# FrontPanel.net
KiCad netlist of a schematic drawn in Altium Designer
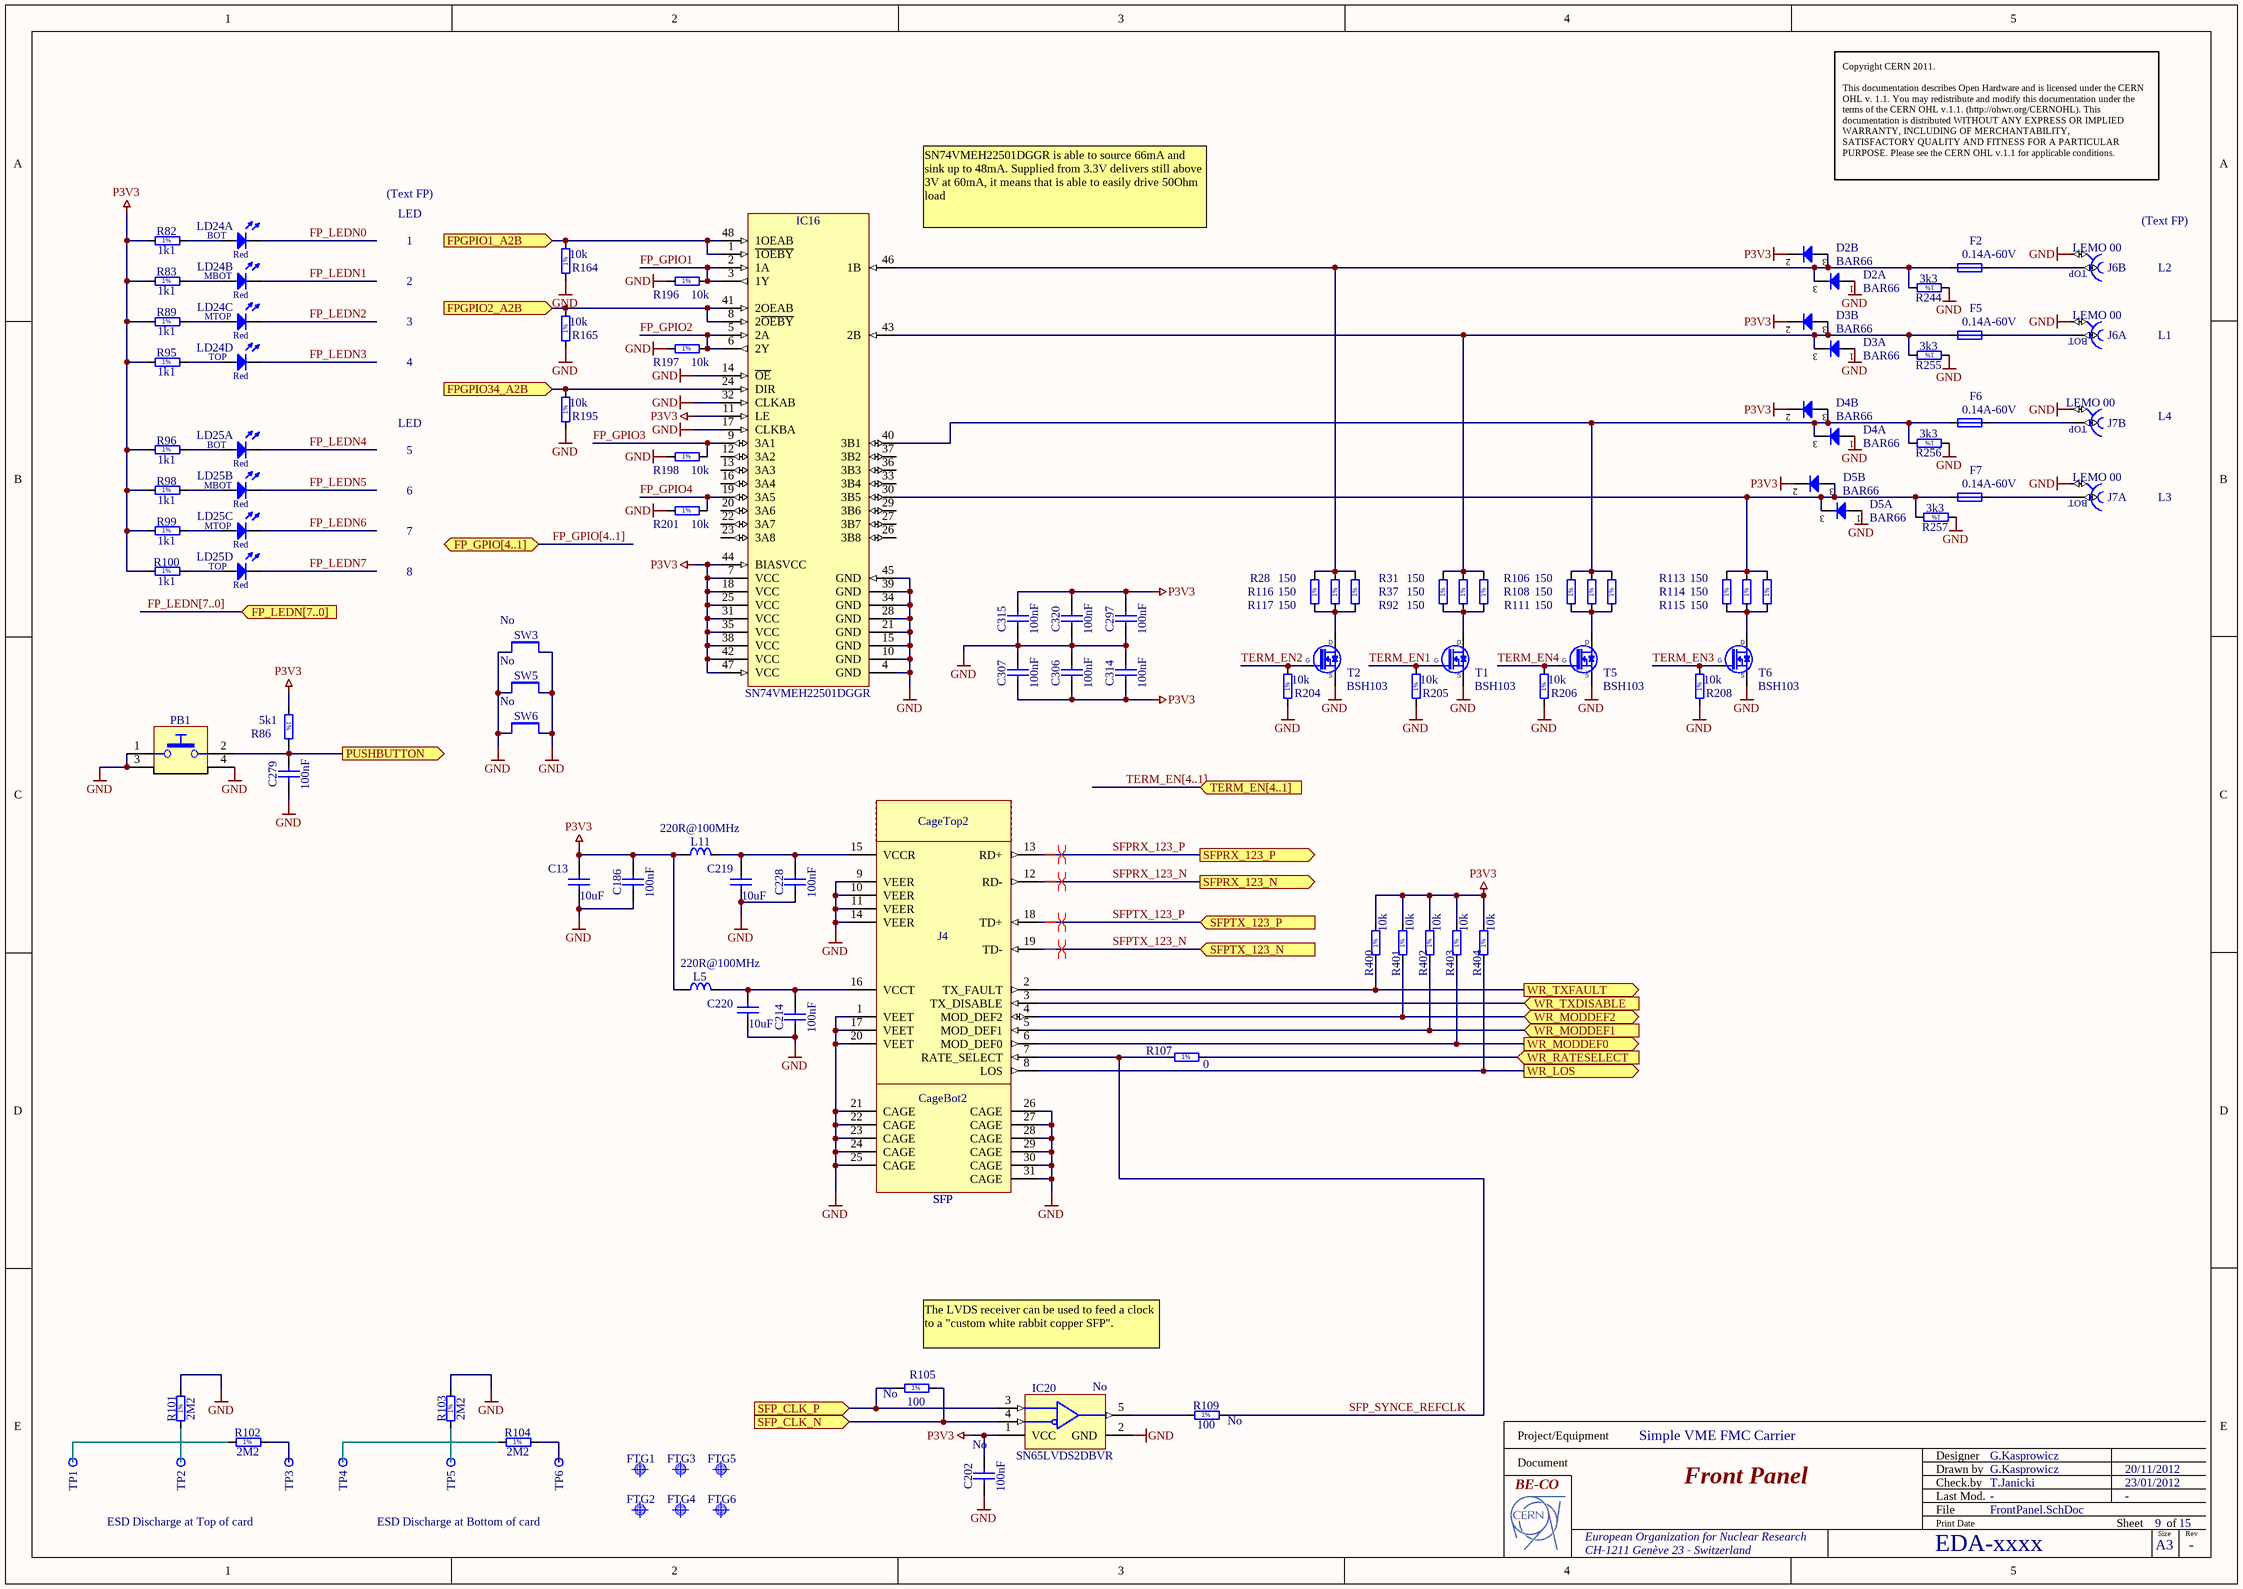
[diagram p0: FrontPanel.SchDoc]

(export (version "E")
  (design (tool "Eeschema 10.0.6"))
  (components
    (comp (ref "C13")
      (value "10uF")
      (footprint "CAPC3225X270N")
      (description "Non-polarised capacitor")
      (fields (field (name "PART NUMBER") "CC1210_10UF_25V_10%_X7R") (field (name "VOLTAGE") "25V"))
      (libsource (lib "Capacitors") (part "Capacitor - non polarized"))
    )
    (comp (ref "C186")
      (value "100nF")
      (footprint "CAPC1005X55N")
      (description "Non-polarised capacitor")
      (fields (field (name "PART NUMBER") "CC0402_100NF_16V_10%_X7R") (field (name "VOLTAGE") "16V"))
      (libsource (lib "Capacitors") (part "Capacitor - non polarized"))
    )
    (comp (ref "C202")
      (value "100nF")
      (footprint "CAPC1005X55N")
      (description "Non-polarised capacitor")
      (fields
        (field (name "PART NUMBER") "CC0402_100NF_16V_10%_X7R")
        (field (name "VOLTAGE") "16V")
        (field (name "MOUNTED") "No")
      )
      (libsource (lib "Capacitors") (part "Capacitor - non polarized"))
    )
    (comp (ref "C214")
      (value "100nF")
      (footprint "CAPC1005X55N")
      (description "Non-polarised capacitor")
      (fields (field (name "PART NUMBER") "CC0402_100NF_16V_10%_X7R") (field (name "VOLTAGE") "16V"))
      (libsource (lib "Capacitors") (part "Capacitor - non polarized"))
    )
    (comp (ref "C219")
      (value "10uF")
      (footprint "CAPC3225X270N")
      (description "Non-polarised capacitor")
      (fields (field (name "PART NUMBER") "CC1210_10UF_25V_10%_X7R") (field (name "VOLTAGE") "25V"))
      (libsource (lib "Capacitors") (part "Capacitor - non polarized"))
    )
    (comp (ref "C220")
      (value "10uF")
      (footprint "CAPC3225X270N")
      (description "Non-polarised capacitor")
      (fields (field (name "PART NUMBER") "CC1210_10UF_25V_10%_X7R") (field (name "VOLTAGE") "25V"))
      (libsource (lib "Capacitors") (part "Capacitor - non polarized"))
    )
    (comp (ref "C228")
      (value "100nF")
      (footprint "CAPC1005X55N")
      (description "Non-polarised capacitor")
      (fields (field (name "PART NUMBER") "CC0402_100NF_16V_10%_X7R") (field (name "VOLTAGE") "16V"))
      (libsource (lib "Capacitors") (part "Capacitor - non polarized"))
    )
    (comp (ref "C279")
      (value "100nF")
      (footprint "CAPC1005X55N")
      (description "Non-polarised capacitor")
      (fields (field (name "PART NUMBER") "CC0402_100NF_16V_10%_X7R") (field (name "VOLTAGE") "16V"))
      (libsource (lib "Capacitors") (part "Capacitor - non polarized"))
    )
    (comp (ref "C297")
      (value "100nF")
      (footprint "CAPC1005X55N")
      (description "Non-polarised capacitor")
      (fields (field (name "PART NUMBER") "CC0402_100NF_16V_10%_X7R") (field (name "VOLTAGE") "16V"))
      (libsource (lib "Capacitors") (part "Capacitor - non polarized"))
    )
    (comp (ref "C306")
      (value "100nF")
      (footprint "CAPC1005X55N")
      (description "Non-polarised capacitor")
      (fields (field (name "PART NUMBER") "CC0402_100NF_16V_10%_X7R") (field (name "VOLTAGE") "16V"))
      (libsource (lib "Capacitors") (part "Capacitor - non polarized"))
    )
    (comp (ref "C307")
      (value "100nF")
      (footprint "CAPC1005X55N")
      (description "Non-polarised capacitor")
      (fields (field (name "PART NUMBER") "CC0402_100NF_16V_10%_X7R") (field (name "VOLTAGE") "16V"))
      (libsource (lib "Capacitors") (part "Capacitor - non polarized"))
    )
    (comp (ref "C314")
      (value "100nF")
      (footprint "CAPC1005X55N")
      (description "Non-polarised capacitor")
      (fields (field (name "PART NUMBER") "CC0402_100NF_16V_10%_X7R") (field (name "VOLTAGE") "16V"))
      (libsource (lib "Capacitors") (part "Capacitor - non polarized"))
    )
    (comp (ref "C315")
      (value "100nF")
      (footprint "CAPC1005X55N")
      (description "Non-polarised capacitor")
      (fields (field (name "PART NUMBER") "CC0402_100NF_16V_10%_X7R") (field (name "VOLTAGE") "16V"))
      (libsource (lib "Capacitors") (part "Capacitor - non polarized"))
    )
    (comp (ref "C320")
      (value "100nF")
      (footprint "CAPC1005X55N")
      (description "Non-polarised capacitor")
      (fields (field (name "PART NUMBER") "CC0402_100NF_16V_10%_X7R") (field (name "VOLTAGE") "16V"))
      (libsource (lib "Capacitors") (part "Capacitor - non polarized"))
    )
    (comp (ref "CageBot2")
      (value "SFP")
      (footprint "TYCO_6367034-1")
      (description "SFP  Cage Bottom (Small Form-factor Pluggable)")
      (fields (field (name "PART NUMBER") "TYCO_6367034-1") (field (name "MANUFACTURER") "TYCO ELECTRONICS"))
      (libsource (lib "Connectors") (part "SFPx1_Cage Bottom"))
    )
    (comp (ref "CageTop2")
      (value "SFP")
      (footprint "TYCO_6367035-1")
      (description "SFP  Cage Top (Small Form-factor Pluggable)")
      (fields (field (name "PART NUMBER") "TYCO_6367035-1") (field (name "MANUFACTURER") "TYCO ELECTRONICS"))
      (libsource (lib "Connectors") (part "SFPx1_Cage Top"))
    )
    (comp (ref "D2")
      (value "BAR66")
      (footprint "SOT95P240X110-3N")
      (description "Serial Diode")
      (fields (field (name "VOLTAGE") "150V") (field (name "POWER") "250mA"))
      (libsource (lib "ICs And Semiconductors") (part "Diode x2 A1C3_A3C2"))
    )
    (comp (ref "D3")
      (value "BAR66")
      (footprint "SOT95P240X110-3N")
      (description "Serial Diode")
      (fields (field (name "VOLTAGE") "150V") (field (name "POWER") "250mA"))
      (libsource (lib "ICs And Semiconductors") (part "Diode x2 A1C3_A3C2"))
    )
    (comp (ref "D4")
      (value "BAR66")
      (footprint "SOT95P240X110-3N")
      (description "Serial Diode")
      (fields (field (name "VOLTAGE") "150V") (field (name "POWER") "250mA"))
      (libsource (lib "ICs And Semiconductors") (part "Diode x2 A1C3_A3C2"))
    )
    (comp (ref "D5")
      (value "BAR66")
      (footprint "SOT95P240X110-3N")
      (description "Serial Diode")
      (fields (field (name "VOLTAGE") "150V") (field (name "POWER") "250mA"))
      (libsource (lib "ICs And Semiconductors") (part "Diode x2 A1C3_A3C2"))
    )
    (comp (ref "F2")
      (value "0.14A-60V")
      (footprint "FUSRC4632X90N")
      (description "Fuse")
      (fields
        (field (name "PART NUMBER") "FUSR1812_TYCO-miniSMD0114F")
        (field (name "MANUFACTURER") "TYCO ELECTRONICS")
      )
      (libsource (lib "Eletro-mechanical") (part "Fuse"))
    )
    (comp (ref "F5")
      (value "0.14A-60V")
      (footprint "FUSRC4632X90N")
      (description "Fuse")
      (fields
        (field (name "PART NUMBER") "FUSR1812_TYCO-miniSMD0114F")
        (field (name "MANUFACTURER") "TYCO ELECTRONICS")
      )
      (libsource (lib "Eletro-mechanical") (part "Fuse"))
    )
    (comp (ref "F6")
      (value "0.14A-60V")
      (footprint "FUSRC4632X90N")
      (description "Fuse")
      (fields
        (field (name "PART NUMBER") "FUSR1812_TYCO-miniSMD0114F")
        (field (name "MANUFACTURER") "TYCO ELECTRONICS")
      )
      (libsource (lib "Eletro-mechanical") (part "Fuse"))
    )
    (comp (ref "F7")
      (value "0.14A-60V")
      (footprint "FUSRC4632X90N")
      (description "Fuse")
      (fields
        (field (name "PART NUMBER") "FUSR1812_TYCO-miniSMD0114F")
        (field (name "MANUFACTURER") "TYCO ELECTRONICS")
      )
      (libsource (lib "Eletro-mechanical") (part "Fuse"))
    )
    (comp (ref "FTG1")
      (value "Use only in PCB")
      (footprint "FIDUCIAL_TOP_S100-200")
      (description "Fiducial Target")
      (fields (field (name "PART NUMBER") "FIDUCIAL_TARGET_S100-200"))
      (libsource (lib "Eletro-mechanical") (part "Fiducial Target"))
    )
    (comp (ref "FTG2")
      (value "Use only in PCB")
      (footprint "FIDUCIAL_TOP_S100-200")
      (description "Fiducial Target")
      (fields (field (name "PART NUMBER") "FIDUCIAL_TARGET_S100-200"))
      (libsource (lib "Eletro-mechanical") (part "Fiducial Target"))
    )
    (comp (ref "FTG3")
      (value "Use only in PCB")
      (footprint "FIDUCIAL_TOP_S100-200")
      (description "Fiducial Target")
      (fields (field (name "PART NUMBER") "FIDUCIAL_TARGET_S100-200"))
      (libsource (lib "Eletro-mechanical") (part "Fiducial Target"))
    )
    (comp (ref "FTG4")
      (value "Use only in PCB")
      (footprint "FIDUCIAL_TOP_S100-200")
      (description "Fiducial Target")
      (fields (field (name "PART NUMBER") "FIDUCIAL_TARGET_S100-200"))
      (libsource (lib "Eletro-mechanical") (part "Fiducial Target"))
    )
    (comp (ref "FTG5")
      (value "Use only in PCB")
      (footprint "FIDUCIAL_TOP_S100-200")
      (description "Fiducial Target")
      (fields (field (name "PART NUMBER") "FIDUCIAL_TARGET_S100-200"))
      (libsource (lib "Eletro-mechanical") (part "Fiducial Target"))
    )
    (comp (ref "FTG6")
      (value "Use only in PCB")
      (footprint "FIDUCIAL_TOP_S100-200")
      (description "Fiducial Target")
      (fields (field (name "PART NUMBER") "FIDUCIAL_TARGET_S100-200"))
      (libsource (lib "Eletro-mechanical") (part "Fiducial Target"))
    )
    (comp (ref "IC16")
      (value "SN74VMEH22501DGGR")
      (footprint "SOP50P810X120-48N")
      (description "8-Bit Universal Bus Transceiver and Two 1-Bit Bus Transceivers with 3-State Outputs")
      (fields (field (name "MANUFACTURER") "TEXAS INSTRUMENTS"))
      (libsource (lib "ICs And Semiconductors") (part "74VMEH22501"))
    )
    (comp (ref "IC20")
      (value "SN65LVDS2DBVR")
      (footprint "SOT95P280X145-5N")
      (description "High-Speed Differential Line Receiver")
      (fields (field (name "MANUFACTURER") "TEXAS INSTRUMENTS") (field (name "MOUNTED") "No"))
      (libsource (lib "ICs And Semiconductors") (part "SN65LVDS2DBVR"))
    )
    (comp (ref "J4")
      (value "SFP")
      (footprint "TYCO_1367073-1")
      (description "20 Position SFP  Connector (Small Form-factor Pluggable)")
      (fields (field (name "PART NUMBER") "TYCO_1367073-1") (field (name "MANUFACTURER") "TYCO ELECTRONICS"))
      (libsource (lib "Connectors") (part "SFPx1"))
    )
    (comp (ref "J6")
      (value "LEMO 00")
      (footprint "LEMO_EPY.00.250.NTNY")
      (description "Dual Female Coax 1-2 Common Shield 3")
      (fields (field (name "PART NUMBER") "LEMO_EPY.00.250.NTNY") (field (name "MANUFACTURER") "LEMO"))
      (libsource (lib "Connectors") (part "LEMO_EPY.00.250.NTN"))
    )
    (comp (ref "J7")
      (value "LEMO 00")
      (footprint "LEMO_EPY.00.250.NTNY")
      (description "Dual Female Coax 1-2 Common Shield 3")
      (fields (field (name "PART NUMBER") "LEMO_EPY.00.250.NTNY") (field (name "MANUFACTURER") "LEMO"))
      (libsource (lib "Connectors") (part "LEMO_EPY.00.250.NTN"))
    )
    (comp (ref "L5")
      (value "220R@100MHz")
      (footprint "INDC2012X105N")
      (description "Inductor")
      (fields (field (name "PART NUMBER") "IND0805_MURATA_BLM21PG221SN1D") (field (name "POWER") "2A"))
      (libsource (lib "Inductors & Transformers") (part "Inductor"))
    )
    (comp (ref "L11")
      (value "220R@100MHz")
      (footprint "INDC2012X105N")
      (description "Inductor")
      (fields (field (name "PART NUMBER") "IND0805_MURATA_BLM21PG221SN1D") (field (name "POWER") "2A"))
      (libsource (lib "Inductors & Transformers") (part "Inductor"))
    )
    (comp (ref "LD24")
      (value "HE Red")
      (footprint "LED_BIVAR_H485CHDL")
      (description "LED x4 Red 1C2A-BOT_3C4A_5C6A_7C8A-TOP")
      (fields (field (name "PART NUMBER") "LED_BIVAR_H485CHDL") (field (name "MANUFACTURER") "BIVAR"))
      (libsource (lib "ICs And Semiconductors") (part "LED x4 Red 1C2A-BOT_3C4A_5C6A_7C8A-TOP"))
    )
    (comp (ref "LD25")
      (value "HE Red")
      (footprint "LED_BIVAR_H485CHDL")
      (description "LED x4 Red 1C2A-BOT_3C4A_5C6A_7C8A-TOP")
      (fields (field (name "PART NUMBER") "LED_BIVAR_H485CHDL") (field (name "MANUFACTURER") "BIVAR"))
      (libsource (lib "ICs And Semiconductors") (part "LED x4 Red 1C2A-BOT_3C4A_5C6A_7C8A-TOP"))
    )
    (comp (ref "PB1")
      (value "Push Button")
      (footprint "PB_ALPS_SKHHLQA010")
      (description "Push-Button Switch SPDT")
      (fields (field (name "PART NUMBER") "PB_ALPS_SKHHLQA010") (field (name "MANUFACTURER") "ALPS"))
      (libsource (lib "Eletro-mechanical") (part "PB SPST 1NO-2NO 34CASE"))
    )
    (comp (ref "R28")
      (value "150")
      (footprint "RESC3216X65N")
      (description "Resistor - 1%")
      (fields (field (name "PART NUMBER") "R1206_150R_1%_0.25W_100PPM") (field (name "POWER") "0.25W"))
      (libsource (lib "Resistors") (part "Resistor - 1%"))
    )
    (comp (ref "R31")
      (value "150")
      (footprint "RESC3216X65N")
      (description "Resistor - 1%")
      (fields (field (name "PART NUMBER") "R1206_150R_1%_0.25W_100PPM") (field (name "POWER") "0.25W"))
      (libsource (lib "Resistors") (part "Resistor - 1%"))
    )
    (comp (ref "R37")
      (value "150")
      (footprint "RESC3216X65N")
      (description "Resistor - 1%")
      (fields (field (name "PART NUMBER") "R1206_150R_1%_0.25W_100PPM") (field (name "POWER") "0.25W"))
      (libsource (lib "Resistors") (part "Resistor - 1%"))
    )
    (comp (ref "R82")
      (value "1k1")
      (footprint "RESC1608X55N")
      (description "Resistor - 1%")
      (fields (field (name "PART NUMBER") "R0603_1K1_1%_0.1W_100PPM") (field (name "POWER") "0.1W"))
      (libsource (lib "Resistors") (part "Resistor - 1%"))
    )
    (comp (ref "R83")
      (value "1k1")
      (footprint "RESC1608X55N")
      (description "Resistor - 1%")
      (fields (field (name "PART NUMBER") "R0603_1K1_1%_0.1W_100PPM") (field (name "POWER") "0.1W"))
      (libsource (lib "Resistors") (part "Resistor - 1%"))
    )
    (comp (ref "R86")
      (value "5k1")
      (footprint "RESC1608X55N")
      (description "Resistor - 1%")
      (fields (field (name "PART NUMBER") "R0603_5K1_1%_0.1W_100PPM") (field (name "POWER") "0.1W"))
      (libsource (lib "Resistors") (part "Resistor - 1%"))
    )
    (comp (ref "R89")
      (value "1k1")
      (footprint "RESC1608X55N")
      (description "Resistor - 1%")
      (fields (field (name "PART NUMBER") "R0603_1K1_1%_0.1W_100PPM") (field (name "POWER") "0.1W"))
      (libsource (lib "Resistors") (part "Resistor - 1%"))
    )
    (comp (ref "R92")
      (value "150")
      (footprint "RESC3216X65N")
      (description "Resistor - 1%")
      (fields (field (name "PART NUMBER") "R1206_150R_1%_0.25W_100PPM") (field (name "POWER") "0.25W"))
      (libsource (lib "Resistors") (part "Resistor - 1%"))
    )
    (comp (ref "R95")
      (value "1k1")
      (footprint "RESC1608X55N")
      (description "Resistor - 1%")
      (fields (field (name "PART NUMBER") "R0603_1K1_1%_0.1W_100PPM") (field (name "POWER") "0.1W"))
      (libsource (lib "Resistors") (part "Resistor - 1%"))
    )
    (comp (ref "R96")
      (value "1k1")
      (footprint "RESC1608X55N")
      (description "Resistor - 1%")
      (fields (field (name "PART NUMBER") "R0603_1K1_1%_0.1W_100PPM") (field (name "POWER") "0.1W"))
      (libsource (lib "Resistors") (part "Resistor - 1%"))
    )
    (comp (ref "R98")
      (value "1k1")
      (footprint "RESC1608X55N")
      (description "Resistor - 1%")
      (fields (field (name "PART NUMBER") "R0603_1K1_1%_0.1W_100PPM") (field (name "POWER") "0.1W"))
      (libsource (lib "Resistors") (part "Resistor - 1%"))
    )
    (comp (ref "R99")
      (value "1k1")
      (footprint "RESC1608X55N")
      (description "Resistor - 1%")
      (fields (field (name "PART NUMBER") "R0603_1K1_1%_0.1W_100PPM") (field (name "POWER") "0.1W"))
      (libsource (lib "Resistors") (part "Resistor - 1%"))
    )
    (comp (ref "R100")
      (value "1k1")
      (footprint "RESC1608X55N")
      (description "Resistor - 1%")
      (fields (field (name "PART NUMBER") "R0603_1K1_1%_0.1W_100PPM") (field (name "POWER") "0.1W"))
      (libsource (lib "Resistors") (part "Resistor - 1%"))
    )
    (comp (ref "R101")
      (value "2M2")
      (footprint "RESC2012X60N")
      (description "Resistor - 1%")
      (fields (field (name "PART NUMBER") "R0805_2M2_1%_0.125W_100PPM") (field (name "POWER") "0.125W"))
      (libsource (lib "Resistors") (part "Resistor - 1%"))
    )
    (comp (ref "R102")
      (value "2M2")
      (footprint "RESC2012X60N")
      (description "Resistor - 1%")
      (fields (field (name "PART NUMBER") "R0805_2M2_1%_0.125W_100PPM") (field (name "POWER") "0.125W"))
      (libsource (lib "Resistors") (part "Resistor - 1%"))
    )
    (comp (ref "R103")
      (value "2M2")
      (footprint "RESC2012X60N")
      (description "Resistor - 1%")
      (fields (field (name "PART NUMBER") "R0805_2M2_1%_0.125W_100PPM") (field (name "POWER") "0.125W"))
      (libsource (lib "Resistors") (part "Resistor - 1%"))
    )
    (comp (ref "R104")
      (value "2M2")
      (footprint "RESC2012X60N")
      (description "Resistor - 1%")
      (fields (field (name "PART NUMBER") "R0805_2M2_1%_0.125W_100PPM") (field (name "POWER") "0.125W"))
      (libsource (lib "Resistors") (part "Resistor - 1%"))
    )
    (comp (ref "R105")
      (value "100")
      (footprint "RESC1608X55N")
      (description "Resistor - 1%")
      (fields
        (field (name "PART NUMBER") "R0603_100R_1%_0.1W_100PPM")
        (field (name "POWER") "0.1W")
        (field (name "MOUNTED") "No")
      )
      (libsource (lib "Resistors") (part "Resistor - 1%"))
    )
    (comp (ref "R106")
      (value "150")
      (footprint "RESC3216X65N")
      (description "Resistor - 1%")
      (fields (field (name "PART NUMBER") "R1206_150R_1%_0.25W_100PPM") (field (name "POWER") "0.25W"))
      (libsource (lib "Resistors") (part "Resistor - 1%"))
    )
    (comp (ref "R107")
      (value "0")
      (footprint "RESC1608X55N")
      (description "Resistor - 1%")
      (fields (field (name "PART NUMBER") "R0603_0R_JUMPER") (field (name "MANUFACTURER") "GENERIC"))
      (libsource (lib "Resistors") (part "Resistor - 1%"))
    )
    (comp (ref "R108")
      (value "150")
      (footprint "RESC3216X65N")
      (description "Resistor - 1%")
      (fields (field (name "PART NUMBER") "R1206_150R_1%_0.25W_100PPM") (field (name "POWER") "0.25W"))
      (libsource (lib "Resistors") (part "Resistor - 1%"))
    )
    (comp (ref "R109")
      (value "100")
      (footprint "RESC1608X55N")
      (description "Resistor - 1%")
      (fields
        (field (name "PART NUMBER") "R0603_100R_1%_0.1W_100PPM")
        (field (name "POWER") "0.1W")
        (field (name "MOUNTED") "No")
      )
      (libsource (lib "Resistors") (part "Resistor - 1%"))
    )
    (comp (ref "R111")
      (value "150")
      (footprint "RESC3216X65N")
      (description "Resistor - 1%")
      (fields (field (name "PART NUMBER") "R1206_150R_1%_0.25W_100PPM") (field (name "POWER") "0.25W"))
      (libsource (lib "Resistors") (part "Resistor - 1%"))
    )
    (comp (ref "R113")
      (value "150")
      (footprint "RESC3216X65N")
      (description "Resistor - 1%")
      (fields (field (name "PART NUMBER") "R1206_150R_1%_0.25W_100PPM") (field (name "POWER") "0.25W"))
      (libsource (lib "Resistors") (part "Resistor - 1%"))
    )
    (comp (ref "R114")
      (value "150")
      (footprint "RESC3216X65N")
      (description "Resistor - 1%")
      (fields (field (name "PART NUMBER") "R1206_150R_1%_0.25W_100PPM") (field (name "POWER") "0.25W"))
      (libsource (lib "Resistors") (part "Resistor - 1%"))
    )
    (comp (ref "R115")
      (value "150")
      (footprint "RESC3216X65N")
      (description "Resistor - 1%")
      (fields (field (name "PART NUMBER") "R1206_150R_1%_0.25W_100PPM") (field (name "POWER") "0.25W"))
      (libsource (lib "Resistors") (part "Resistor - 1%"))
    )
    (comp (ref "R116")
      (value "150")
      (footprint "RESC3216X65N")
      (description "Resistor - 1%")
      (fields (field (name "PART NUMBER") "R1206_150R_1%_0.25W_100PPM") (field (name "POWER") "0.25W"))
      (libsource (lib "Resistors") (part "Resistor - 1%"))
    )
    (comp (ref "R117")
      (value "150")
      (footprint "RESC3216X65N")
      (description "Resistor - 1%")
      (fields (field (name "PART NUMBER") "R1206_150R_1%_0.25W_100PPM") (field (name "POWER") "0.25W"))
      (libsource (lib "Resistors") (part "Resistor - 1%"))
    )
    (comp (ref "R164")
      (value "10k")
      (footprint "RESC1608X55N")
      (description "Resistor - 1%")
      (fields (field (name "PART NUMBER") "R0603_10K_1%_0.1W_100PPM") (field (name "POWER") "0.1W"))
      (libsource (lib "Resistors") (part "Resistor - 1%"))
    )
    (comp (ref "R165")
      (value "10k")
      (footprint "RESC1608X55N")
      (description "Resistor - 1%")
      (fields (field (name "PART NUMBER") "R0603_10K_1%_0.1W_100PPM") (field (name "POWER") "0.1W"))
      (libsource (lib "Resistors") (part "Resistor - 1%"))
    )
    (comp (ref "R195")
      (value "10k")
      (footprint "RESC1608X55N")
      (description "Resistor - 1%")
      (fields (field (name "PART NUMBER") "R0603_10K_1%_0.1W_100PPM") (field (name "POWER") "0.1W"))
      (libsource (lib "Resistors") (part "Resistor - 1%"))
    )
    (comp (ref "R196")
      (value "10k")
      (footprint "RESC1608X55N")
      (description "Resistor - 1%")
      (fields (field (name "PART NUMBER") "R0603_10K_1%_0.1W_100PPM") (field (name "POWER") "0.1W"))
      (libsource (lib "Resistors") (part "Resistor - 1%"))
    )
    (comp (ref "R197")
      (value "10k")
      (footprint "RESC1608X55N")
      (description "Resistor - 1%")
      (fields (field (name "PART NUMBER") "R0603_10K_1%_0.1W_100PPM") (field (name "POWER") "0.1W"))
      (libsource (lib "Resistors") (part "Resistor - 1%"))
    )
    (comp (ref "R198")
      (value "10k")
      (footprint "RESC1608X55N")
      (description "Resistor - 1%")
      (fields (field (name "PART NUMBER") "R0603_10K_1%_0.1W_100PPM") (field (name "POWER") "0.1W"))
      (libsource (lib "Resistors") (part "Resistor - 1%"))
    )
    (comp (ref "R201")
      (value "10k")
      (footprint "RESC1608X55N")
      (description "Resistor - 1%")
      (fields (field (name "PART NUMBER") "R0603_10K_1%_0.1W_100PPM") (field (name "POWER") "0.1W"))
      (libsource (lib "Resistors") (part "Resistor - 1%"))
    )
    (comp (ref "R204")
      (value "10k")
      (footprint "RESC1608X55N")
      (description "Resistor - 1%")
      (fields (field (name "PART NUMBER") "R0603_10K_1%_0.1W_100PPM") (field (name "POWER") "0.1W"))
      (libsource (lib "Resistors") (part "Resistor - 1%"))
    )
    (comp (ref "R205")
      (value "10k")
      (footprint "RESC1608X55N")
      (description "Resistor - 1%")
      (fields (field (name "PART NUMBER") "R0603_10K_1%_0.1W_100PPM") (field (name "POWER") "0.1W"))
      (libsource (lib "Resistors") (part "Resistor - 1%"))
    )
    (comp (ref "R206")
      (value "10k")
      (footprint "RESC1608X55N")
      (description "Resistor - 1%")
      (fields (field (name "PART NUMBER") "R0603_10K_1%_0.1W_100PPM") (field (name "POWER") "0.1W"))
      (libsource (lib "Resistors") (part "Resistor - 1%"))
    )
    (comp (ref "R208")
      (value "10k")
      (footprint "RESC1608X55N")
      (description "Resistor - 1%")
      (fields (field (name "PART NUMBER") "R0603_10K_1%_0.1W_100PPM") (field (name "POWER") "0.1W"))
      (libsource (lib "Resistors") (part "Resistor - 1%"))
    )
    (comp (ref "R244")
      (value "3k3")
      (footprint "RESC1608X55N")
      (description "Resistor - 1%")
      (fields (field (name "PART NUMBER") "R0603_3K3_1%_0.1W_100PPM") (field (name "POWER") "0.1W"))
      (libsource (lib "Resistors") (part "Resistor - 1%"))
    )
    (comp (ref "R255")
      (value "3k3")
      (footprint "RESC1608X55N")
      (description "Resistor - 1%")
      (fields (field (name "PART NUMBER") "R0603_3K3_1%_0.1W_100PPM") (field (name "POWER") "0.1W"))
      (libsource (lib "Resistors") (part "Resistor - 1%"))
    )
    (comp (ref "R256")
      (value "3k3")
      (footprint "RESC1608X55N")
      (description "Resistor - 1%")
      (fields (field (name "PART NUMBER") "R0603_3K3_1%_0.1W_100PPM") (field (name "POWER") "0.1W"))
      (libsource (lib "Resistors") (part "Resistor - 1%"))
    )
    (comp (ref "R257")
      (value "3k3")
      (footprint "RESC1608X55N")
      (description "Resistor - 1%")
      (fields (field (name "PART NUMBER") "R0603_3K3_1%_0.1W_100PPM") (field (name "POWER") "0.1W"))
      (libsource (lib "Resistors") (part "Resistor - 1%"))
    )
    (comp (ref "R400")
      (value "10k")
      (footprint "RESC1608X55N")
      (description "Resistor - 1%")
      (fields (field (name "PART NUMBER") "R0603_10K_1%_0.1W_100PPM") (field (name "POWER") "0.1W"))
      (libsource (lib "Resistors") (part "Resistor - 1%"))
    )
    (comp (ref "R401")
      (value "10k")
      (footprint "RESC1608X55N")
      (description "Resistor - 1%")
      (fields (field (name "PART NUMBER") "R0603_10K_1%_0.1W_100PPM") (field (name "POWER") "0.1W"))
      (libsource (lib "Resistors") (part "Resistor - 1%"))
    )
    (comp (ref "R402")
      (value "10k")
      (footprint "RESC1608X55N")
      (description "Resistor - 1%")
      (fields (field (name "PART NUMBER") "R0603_10K_1%_0.1W_100PPM") (field (name "POWER") "0.1W"))
      (libsource (lib "Resistors") (part "Resistor - 1%"))
    )
    (comp (ref "R403")
      (value "10k")
      (footprint "RESC1608X55N")
      (description "Resistor - 1%")
      (fields (field (name "PART NUMBER") "R0603_10K_1%_0.1W_100PPM") (field (name "POWER") "0.1W"))
      (libsource (lib "Resistors") (part "Resistor - 1%"))
    )
    (comp (ref "R404")
      (value "10k")
      (footprint "RESC1608X55N")
      (description "Resistor - 1%")
      (fields (field (name "PART NUMBER") "R0603_10K_1%_0.1W_100PPM") (field (name "POWER") "0.1W"))
      (libsource (lib "Resistors") (part "Resistor - 1%"))
    )
    (comp (ref "SW3")
      (value "Jumper Type2")
      (footprint "COMATEL_313.0004.0.00.500")
      (description "Jumper 2 pins")
      (fields
        (field (name "PART NUMBER") "COMATEL_313.0004.0.00.500")
        (field (name "MOUNTED") "No")
        (field (name "MANUFACTURER") "KONTEK COMATEL")
      )
      (libsource (lib "Connectors") (part "Jumper Type2"))
    )
    (comp (ref "SW5")
      (value "Jumper Type2")
      (footprint "COMATEL_313.0004.0.00.500")
      (description "Jumper 2 pins")
      (fields
        (field (name "PART NUMBER") "COMATEL_313.0004.0.00.500")
        (field (name "MOUNTED") "No")
        (field (name "MANUFACTURER") "KONTEK COMATEL")
      )
      (libsource (lib "Connectors") (part "Jumper Type2"))
    )
    (comp (ref "SW6")
      (value "Jumper Type2")
      (footprint "COMATEL_313.0004.0.00.500")
      (description "Jumper 2 pins")
      (fields
        (field (name "PART NUMBER") "COMATEL_313.0004.0.00.500")
        (field (name "MOUNTED") "No")
        (field (name "MANUFACTURER") "KONTEK COMATEL")
      )
      (libsource (lib "Connectors") (part "Jumper Type2"))
    )
    (comp (ref "T1")
      (value "BSH103")
      (footprint "SOT95P230X110-3N")
      (description "N-CHANNEL MOSFET WITH DIODE")
      (fields (field (name "MANUFACTURER") "NXP SEMICONDUCTORS"))
      (libsource (lib "ICs And Semiconductors") (part "N-MOSFET-D 1G 2S 3D"))
    )
    (comp (ref "T2")
      (value "BSH103")
      (footprint "SOT95P230X110-3N")
      (description "N-CHANNEL MOSFET WITH DIODE")
      (fields (field (name "MANUFACTURER") "NXP SEMICONDUCTORS"))
      (libsource (lib "ICs And Semiconductors") (part "N-MOSFET-D 1G 2S 3D"))
    )
    (comp (ref "T5")
      (value "BSH103")
      (footprint "SOT95P230X110-3N")
      (description "N-CHANNEL MOSFET WITH DIODE")
      (fields (field (name "MANUFACTURER") "NXP SEMICONDUCTORS"))
      (libsource (lib "ICs And Semiconductors") (part "N-MOSFET-D 1G 2S 3D"))
    )
    (comp (ref "T6")
      (value "BSH103")
      (footprint "SOT95P230X110-3N")
      (description "N-CHANNEL MOSFET WITH DIODE")
      (fields (field (name "MANUFACTURER") "NXP SEMICONDUCTORS"))
      (libsource (lib "ICs And Semiconductors") (part "N-MOSFET-D 1G 2S 3D"))
    )
    (comp (ref "TP1")
      (value "Test Point")
      (footprint "TPS127")
      (fields (field (name "PART NUMBER") "SMD_PAD_1.27X1.27MM"))
      (libsource (lib "Eletro-mechanical") (part "Test Point"))
    )
    (comp (ref "TP2")
      (value "Test Point")
      (footprint "TPS127")
      (fields (field (name "PART NUMBER") "SMD_PAD_1.27X1.27MM"))
      (libsource (lib "Eletro-mechanical") (part "Test Point"))
    )
    (comp (ref "TP3")
      (value "Test Point")
      (footprint "TPS127")
      (fields (field (name "PART NUMBER") "SMD_PAD_1.27X1.27MM"))
      (libsource (lib "Eletro-mechanical") (part "Test Point"))
    )
    (comp (ref "TP4")
      (value "Test Point")
      (footprint "TPS127")
      (fields (field (name "PART NUMBER") "SMD_PAD_1.27X1.27MM"))
      (libsource (lib "Eletro-mechanical") (part "Test Point"))
    )
    (comp (ref "TP5")
      (value "Test Point")
      (footprint "TPS127")
      (fields (field (name "PART NUMBER") "SMD_PAD_1.27X1.27MM"))
      (libsource (lib "Eletro-mechanical") (part "Test Point"))
    )
    (comp (ref "TP6")
      (value "Test Point")
      (footprint "TPS127")
      (fields (field (name "PART NUMBER") "SMD_PAD_1.27X1.27MM"))
      (libsource (lib "Eletro-mechanical") (part "Test Point"))
    )
  )
  (nets
    (net (code "1") (name "/FPGPIO1_A2B") (class "Default")
      (node (ref "IC16") (pin "1") (pinfunction "~{1OEBY}_1") (pintype "input"))
      (node (ref "IC16") (pin "48") (pinfunction "1OEAB_48") (pintype "input"))
      (node (ref "R164") (pin "2") (pinfunction "2_2") (pintype "passive"))
    )
    (net (code "2") (name "/FPGPIO2_A2B") (class "Default")
      (node (ref "IC16") (pin "41") (pinfunction "2OEAB_41") (pintype "input"))
      (node (ref "IC16") (pin "8") (pinfunction "2~{OEBY}_8") (pintype "input"))
      (node (ref "R165") (pin "2") (pinfunction "2_2") (pintype "passive"))
    )
    (net (code "3") (name "/FPGPIO34_A2B") (class "Default")
      (node (ref "IC16") (pin "24") (pinfunction "DIR_24") (pintype "input"))
      (node (ref "R195") (pin "2") (pinfunction "2_2") (pintype "passive"))
    )
    (net (code "4") (name "/FP_GPIO1") (class "Default")
      (node (ref "IC16") (pin "2") (pinfunction "1A_2") (pintype "input"))
      (node (ref "IC16") (pin "3") (pinfunction "1Y_3") (pintype "output"))
      (node (ref "R196") (pin "2") (pinfunction "2_2") (pintype "passive"))
    )
    (net (code "5") (name "/FP_GPIO2") (class "Default")
      (node (ref "IC16") (pin "5") (pinfunction "2A_5") (pintype "input"))
      (node (ref "IC16") (pin "6") (pinfunction "2Y_6") (pintype "output"))
      (node (ref "R197") (pin "2") (pinfunction "2_2") (pintype "passive"))
    )
    (net (code "6") (name "/FP_GPIO3") (class "Default")
      (node (ref "IC16") (pin "9") (pinfunction "3A1_9") (pintype "bidirectional"))
      (node (ref "R198") (pin "2") (pinfunction "2_2") (pintype "passive"))
    )
    (net (code "7") (name "/FP_GPIO4") (class "Default")
      (node (ref "IC16") (pin "19") (pinfunction "3A5_19") (pintype "bidirectional"))
      (node (ref "R201") (pin "2") (pinfunction "2_2") (pintype "passive"))
    )
    (net (code "9") (name "/FP_LEDN0") (class "Default")
      (node (ref "LD24") (pin "1") (pinfunction "C_1") (pintype "passive"))
    )
    (net (code "10") (name "/FP_LEDN1") (class "Default")
      (node (ref "LD24") (pin "3") (pinfunction "C_3") (pintype "passive"))
    )
    (net (code "11") (name "/FP_LEDN2") (class "Default")
      (node (ref "LD24") (pin "5") (pinfunction "C_5") (pintype "passive"))
    )
    (net (code "12") (name "/FP_LEDN3") (class "Default")
      (node (ref "LD24") (pin "7") (pinfunction "C_7") (pintype "passive"))
    )
    (net (code "13") (name "/FP_LEDN4") (class "Default")
      (node (ref "LD25") (pin "1") (pinfunction "C_1") (pintype "passive"))
    )
    (net (code "14") (name "/FP_LEDN5") (class "Default")
      (node (ref "LD25") (pin "3") (pinfunction "C_3") (pintype "passive"))
    )
    (net (code "15") (name "/FP_LEDN6") (class "Default")
      (node (ref "LD25") (pin "5") (pinfunction "C_5") (pintype "passive"))
    )
    (net (code "16") (name "/FP_LEDN7") (class "Default")
      (node (ref "LD25") (pin "7") (pinfunction "C_7") (pintype "passive"))
    )
    (net (code "18") (name "/PUSHBUTTON") (class "Default")
      (node (ref "C279") (pin "2") (pinfunction "2_2") (pintype "passive"))
      (node (ref "PB1") (pin "2") (pinfunction "2_2") (pintype "passive"))
      (node (ref "R86") (pin "2") (pinfunction "2_2") (pintype "passive"))
    )
    (net (code "19") (name "/SFPRX_123_N") (class "Default")
      (node (ref "J4") (pin "12") (pinfunction "RD-_12") (pintype "output"))
    )
    (net (code "20") (name "/SFPRX_123_P") (class "Default")
      (node (ref "J4") (pin "13") (pinfunction "RD+_13") (pintype "output"))
    )
    (net (code "21") (name "/SFPTX_123_N") (class "Default")
      (node (ref "J4") (pin "19") (pinfunction "TD-_19") (pintype "input"))
    )
    (net (code "22") (name "/SFPTX_123_P") (class "Default")
      (node (ref "J4") (pin "18") (pinfunction "TD+_18") (pintype "input"))
    )
    (net (code "23") (name "/SFP_CLK_N") (class "Default")
      (node (ref "IC20") (pin "4") (pinfunction "B_4") (pintype "input"))
      (node (ref "R105") (pin "2") (pinfunction "2_2") (pintype "passive"))
    )
    (net (code "24") (name "/SFP_CLK_P") (class "Default")
      (node (ref "IC20") (pin "3") (pinfunction "A_3") (pintype "input"))
      (node (ref "R105") (pin "1") (pinfunction "1_1") (pintype "passive"))
    )
    (net (code "25") (name "/SFP_SYNCE_REFCLK") (class "Default")
      (node (ref "J4") (pin "7") (pinfunction "RATE_SELECT_7") (pintype "input"))
      (node (ref "R107") (pin "1") (pinfunction "1_1") (pintype "passive"))
      (node (ref "R109") (pin "2") (pinfunction "2_2") (pintype "passive"))
    )
    (net (code "26") (name "/TERM_EN1") (class "Default")
      (node (ref "R205") (pin "2") (pinfunction "2_2") (pintype "passive"))
      (node (ref "T1") (pin "1") (pinfunction "G_1") (pintype "passive"))
    )
    (net (code "27") (name "/TERM_EN2") (class "Default")
      (node (ref "R204") (pin "2") (pinfunction "2_2") (pintype "passive"))
      (node (ref "T2") (pin "1") (pinfunction "G_1") (pintype "passive"))
    )
    (net (code "28") (name "/TERM_EN3") (class "Default")
      (node (ref "R208") (pin "2") (pinfunction "2_2") (pintype "passive"))
      (node (ref "T6") (pin "1") (pinfunction "G_1") (pintype "passive"))
    )
    (net (code "29") (name "/TERM_EN4") (class "Default")
      (node (ref "R206") (pin "2") (pinfunction "2_2") (pintype "passive"))
      (node (ref "T5") (pin "1") (pinfunction "G_1") (pintype "passive"))
    )
    (net (code "31") (name "/WR_LOS") (class "Default")
      (node (ref "J4") (pin "8") (pinfunction "LOS_8") (pintype "output"))
      (node (ref "R404") (pin "1") (pinfunction "1_1") (pintype "passive"))
    )
    (net (code "32") (name "/WR_MODDEF0") (class "Default")
      (node (ref "J4") (pin "6") (pinfunction "MOD_DEF0_6") (pintype "output"))
      (node (ref "R403") (pin "1") (pinfunction "1_1") (pintype "passive"))
    )
    (net (code "33") (name "/WR_MODDEF1") (class "Default")
      (node (ref "J4") (pin "5") (pinfunction "MOD_DEF1_5") (pintype "input"))
      (node (ref "R402") (pin "1") (pinfunction "1_1") (pintype "passive"))
    )
    (net (code "34") (name "/WR_MODDEF2") (class "Default")
      (node (ref "J4") (pin "4") (pinfunction "MOD_DEF2_4") (pintype "bidirectional"))
      (node (ref "R401") (pin "1") (pinfunction "1_1") (pintype "passive"))
    )
    (net (code "35") (name "/WR_RATESELECT") (class "Default")
      (node (ref "R107") (pin "2") (pinfunction "2_2") (pintype "passive"))
    )
    (net (code "36") (name "/WR_TXDISABLE") (class "Default")
      (node (ref "J4") (pin "3") (pinfunction "TX_DISABLE_3") (pintype "input"))
    )
    (net (code "37") (name "/WR_TXFAULT") (class "Default")
      (node (ref "J4") (pin "2") (pinfunction "TX_FAULT_2") (pintype "output"))
      (node (ref "R400") (pin "1") (pinfunction "1_1") (pintype "passive"))
    )
    (net (code "38") (name "GND") (class "Default")
      (node (ref "C13") (pin "2") (pinfunction "2_2") (pintype "passive"))
      (node (ref "C186") (pin "2") (pinfunction "2_2") (pintype "passive"))
      (node (ref "C202") (pin "1") (pinfunction "1_1") (pintype "passive"))
      (node (ref "C214") (pin "2") (pinfunction "2_2") (pintype "passive"))
      (node (ref "C219") (pin "2") (pinfunction "2_2") (pintype "passive"))
      (node (ref "C220") (pin "2") (pinfunction "2_2") (pintype "passive"))
      (node (ref "C228") (pin "2") (pinfunction "2_2") (pintype "passive"))
      (node (ref "C279") (pin "1") (pinfunction "1_1") (pintype "passive"))
      (node (ref "C297") (pin "1") (pinfunction "1_1") (pintype "passive"))
      (node (ref "C306") (pin "2") (pinfunction "2_2") (pintype "passive"))
      (node (ref "C307") (pin "2") (pinfunction "2_2") (pintype "passive"))
      (node (ref "C314") (pin "2") (pinfunction "2_2") (pintype "passive"))
      (node (ref "C315") (pin "1") (pinfunction "1_1") (pintype "passive"))
      (node (ref "C320") (pin "1") (pinfunction "1_1") (pintype "passive"))
      (node (ref "CageBot2") (pin "21") (pinfunction "CAGE_21") (pintype "power_in"))
      (node (ref "CageBot2") (pin "22") (pinfunction "CAGE_22") (pintype "power_in"))
      (node (ref "CageBot2") (pin "23") (pinfunction "CAGE_23") (pintype "power_in"))
      (node (ref "CageBot2") (pin "24") (pinfunction "CAGE_24") (pintype "power_in"))
      (node (ref "CageBot2") (pin "25") (pinfunction "CAGE_25") (pintype "power_in"))
      (node (ref "CageBot2") (pin "26") (pinfunction "CAGE_26") (pintype "power_in"))
      (node (ref "CageBot2") (pin "27") (pinfunction "CAGE_27") (pintype "power_in"))
      (node (ref "CageBot2") (pin "28") (pinfunction "CAGE_28") (pintype "power_in"))
      (node (ref "CageBot2") (pin "29") (pinfunction "CAGE_29") (pintype "power_in"))
      (node (ref "CageBot2") (pin "30") (pinfunction "CAGE_30") (pintype "power_in"))
      (node (ref "CageBot2") (pin "31") (pinfunction "CAGE_31") (pintype "power_in"))
      (node (ref "D2") (pin "1") (pinfunction "A_1") (pintype "passive"))
      (node (ref "D3") (pin "1") (pinfunction "A_1") (pintype "passive"))
      (node (ref "D4") (pin "1") (pinfunction "A_1") (pintype "passive"))
      (node (ref "D5") (pin "1") (pinfunction "A_1") (pintype "passive"))
      (node (ref "IC16") (pin "10") (pinfunction "GND_10") (pintype "power_in"))
      (node (ref "IC16") (pin "14") (pinfunction "~{OE}_14") (pintype "input"))
      (node (ref "IC16") (pin "15") (pinfunction "GND_15") (pintype "power_in"))
      (node (ref "IC16") (pin "17") (pinfunction "CLKBA_17") (pintype "input"))
      (node (ref "IC16") (pin "21") (pinfunction "GND_21") (pintype "power_in"))
      (node (ref "IC16") (pin "28") (pinfunction "GND_28") (pintype "power_in"))
      (node (ref "IC16") (pin "32") (pinfunction "CLKAB_32") (pintype "input"))
      (node (ref "IC16") (pin "34") (pinfunction "GND_34") (pintype "power_in"))
      (node (ref "IC16") (pin "39") (pinfunction "GND_39") (pintype "power_in"))
      (node (ref "IC16") (pin "4") (pinfunction "GND_4") (pintype "power_in"))
      (node (ref "IC16") (pin "45") (pinfunction "GND_45") (pintype "input"))
      (node (ref "IC20") (pin "2") (pinfunction "GND_2") (pintype "power_in"))
      (node (ref "J4") (pin "1") (pinfunction "VEET_1") (pintype "power_in"))
      (node (ref "J4") (pin "10") (pinfunction "VEER_10") (pintype "power_in"))
      (node (ref "J4") (pin "11") (pinfunction "VEER_11") (pintype "power_in"))
      (node (ref "J4") (pin "14") (pinfunction "VEER_14") (pintype "power_in"))
      (node (ref "J4") (pin "17") (pinfunction "VEET_17") (pintype "power_in"))
      (node (ref "J4") (pin "20") (pinfunction "VEET_20") (pintype "power_in"))
      (node (ref "J4") (pin "9") (pinfunction "VEER_9") (pintype "power_in"))
      (node (ref "J6") (pin "3") (pinfunction "3_3") (pintype "bidirectional"))
      (node (ref "J7") (pin "3") (pinfunction "3_3") (pintype "bidirectional"))
      (node (ref "PB1") (pin "1") (pinfunction "1_1") (pintype "passive"))
      (node (ref "PB1") (pin "3") (pinfunction "3_3") (pintype "passive"))
      (node (ref "PB1") (pin "4") (pinfunction "4_4") (pintype "passive"))
      (node (ref "R101") (pin "2") (pinfunction "2_2") (pintype "passive"))
      (node (ref "R103") (pin "2") (pinfunction "2_2") (pintype "passive"))
      (node (ref "R164") (pin "1") (pinfunction "1_1") (pintype "passive"))
      (node (ref "R165") (pin "1") (pinfunction "1_1") (pintype "passive"))
      (node (ref "R195") (pin "1") (pinfunction "1_1") (pintype "passive"))
      (node (ref "R196") (pin "1") (pinfunction "1_1") (pintype "passive"))
      (node (ref "R197") (pin "1") (pinfunction "1_1") (pintype "passive"))
      (node (ref "R198") (pin "1") (pinfunction "1_1") (pintype "passive"))
      (node (ref "R201") (pin "1") (pinfunction "1_1") (pintype "passive"))
      (node (ref "R204") (pin "1") (pinfunction "1_1") (pintype "passive"))
      (node (ref "R205") (pin "1") (pinfunction "1_1") (pintype "passive"))
      (node (ref "R206") (pin "1") (pinfunction "1_1") (pintype "passive"))
      (node (ref "R208") (pin "1") (pinfunction "1_1") (pintype "passive"))
      (node (ref "R244") (pin "1") (pinfunction "1_1") (pintype "passive"))
      (node (ref "R255") (pin "1") (pinfunction "1_1") (pintype "passive"))
      (node (ref "R256") (pin "1") (pinfunction "1_1") (pintype "passive"))
      (node (ref "R257") (pin "1") (pinfunction "1_1") (pintype "passive"))
      (node (ref "SW3") (pin "1") (pinfunction "1_1") (pintype "bidirectional"))
      (node (ref "SW3") (pin "2") (pinfunction "2_2") (pintype "bidirectional"))
      (node (ref "SW5") (pin "1") (pinfunction "1_1") (pintype "bidirectional"))
      (node (ref "SW5") (pin "2") (pinfunction "2_2") (pintype "bidirectional"))
      (node (ref "SW6") (pin "1") (pinfunction "1_1") (pintype "bidirectional"))
      (node (ref "SW6") (pin "2") (pinfunction "2_2") (pintype "bidirectional"))
      (node (ref "T1") (pin "2") (pinfunction "S_2") (pintype "passive"))
      (node (ref "T2") (pin "2") (pinfunction "S_2") (pintype "passive"))
      (node (ref "T5") (pin "2") (pinfunction "S_2") (pintype "passive"))
      (node (ref "T6") (pin "2") (pinfunction "S_2") (pintype "passive"))
    )
    (net (code "39") (name "Net-(D2A-COMAC)") (class "Default")
      (node (ref "D2") (pin "3") (pinfunction "COMAC_3") (pintype "passive"))
      (node (ref "F2") (pin "1") (pinfunction "1_1") (pintype "passive"))
      (node (ref "IC16") (pin "46") (pinfunction "1B_46") (pintype "input"))
      (node (ref "R116") (pin "2") (pinfunction "2_2") (pintype "passive"))
      (node (ref "R117") (pin "2") (pinfunction "2_2") (pintype "passive"))
      (node (ref "R244") (pin "2") (pinfunction "2_2") (pintype "passive"))
      (node (ref "R28") (pin "2") (pinfunction "2_2") (pintype "passive"))
    )
    (net (code "40") (name "Net-(D3A-COMAC)") (class "Default")
      (node (ref "D3") (pin "3") (pinfunction "COMAC_3") (pintype "passive"))
      (node (ref "F5") (pin "1") (pinfunction "1_1") (pintype "passive"))
      (node (ref "IC16") (pin "43") (pinfunction "2B_43") (pintype "input"))
      (node (ref "R255") (pin "2") (pinfunction "2_2") (pintype "passive"))
      (node (ref "R31") (pin "2") (pinfunction "2_2") (pintype "passive"))
      (node (ref "R37") (pin "2") (pinfunction "2_2") (pintype "passive"))
      (node (ref "R92") (pin "2") (pinfunction "2_2") (pintype "passive"))
    )
    (net (code "41") (name "Net-(D4A-COMAC)") (class "Default")
      (node (ref "D4") (pin "3") (pinfunction "COMAC_3") (pintype "passive"))
      (node (ref "F6") (pin "1") (pinfunction "1_1") (pintype "passive"))
      (node (ref "IC16") (pin "40") (pinfunction "3B1_40") (pintype "bidirectional"))
      (node (ref "R106") (pin "2") (pinfunction "2_2") (pintype "passive"))
      (node (ref "R108") (pin "2") (pinfunction "2_2") (pintype "passive"))
      (node (ref "R111") (pin "2") (pinfunction "2_2") (pintype "passive"))
      (node (ref "R256") (pin "2") (pinfunction "2_2") (pintype "passive"))
    )
    (net (code "42") (name "Net-(D5A-COMAC)") (class "Default")
      (node (ref "D5") (pin "3") (pinfunction "COMAC_3") (pintype "passive"))
      (node (ref "F7") (pin "1") (pinfunction "1_1") (pintype "passive"))
      (node (ref "IC16") (pin "30") (pinfunction "3B5_30") (pintype "bidirectional"))
      (node (ref "R113") (pin "2") (pinfunction "2_2") (pintype "passive"))
      (node (ref "R114") (pin "2") (pinfunction "2_2") (pintype "passive"))
      (node (ref "R115") (pin "2") (pinfunction "2_2") (pintype "passive"))
      (node (ref "R257") (pin "2") (pinfunction "2_2") (pintype "passive"))
    )
    (net (code "43") (name "Net-(F2-Pad2)") (class "Default")
      (node (ref "F2") (pin "2") (pinfunction "2_2") (pintype "passive"))
      (node (ref "J6") (pin "2") (pinfunction "2_2") (pintype "bidirectional"))
    )
    (net (code "44") (name "Net-(F5-Pad2)") (class "Default")
      (node (ref "F5") (pin "2") (pinfunction "2_2") (pintype "passive"))
      (node (ref "J6") (pin "1") (pinfunction "1_1") (pintype "bidirectional"))
    )
    (net (code "45") (name "Net-(F6-Pad2)") (class "Default")
      (node (ref "F6") (pin "2") (pinfunction "2_2") (pintype "passive"))
      (node (ref "J7") (pin "2") (pinfunction "2_2") (pintype "bidirectional"))
    )
    (net (code "46") (name "Net-(F7-Pad2)") (class "Default")
      (node (ref "F7") (pin "2") (pinfunction "2_2") (pintype "passive"))
      (node (ref "J7") (pin "1") (pinfunction "1_1") (pintype "bidirectional"))
    )
    (net (code "47") (name "Net-(IC20-R)") (class "Default")
      (node (ref "IC20") (pin "5") (pinfunction "R_5") (pintype "output"))
      (node (ref "R109") (pin "1") (pinfunction "1_1") (pintype "passive"))
    )
    (net (code "48") (name "Net-(J4-VCCR)") (class "Default")
      (node (ref "C219") (pin "1") (pinfunction "1_1") (pintype "passive"))
      (node (ref "C228") (pin "1") (pinfunction "1_1") (pintype "passive"))
      (node (ref "J4") (pin "15") (pinfunction "VCCR_15") (pintype "power_in"))
      (node (ref "L11") (pin "2") (pinfunction "2_2") (pintype "passive"))
    )
    (net (code "49") (name "Net-(J4-VCCT)") (class "Default")
      (node (ref "C214") (pin "1") (pinfunction "1_1") (pintype "passive"))
      (node (ref "C220") (pin "1") (pinfunction "1_1") (pintype "passive"))
      (node (ref "J4") (pin "16") (pinfunction "VCCT_16") (pintype "power_in"))
      (node (ref "L5") (pin "2") (pinfunction "2_2") (pintype "passive"))
    )
    (net (code "50") (name "Net-(LD24A-A)") (class "Default")
      (node (ref "LD24") (pin "2") (pinfunction "A_2") (pintype "passive"))
      (node (ref "R82") (pin "2") (pinfunction "2_2") (pintype "passive"))
    )
    (net (code "51") (name "Net-(LD24B-A)") (class "Default")
      (node (ref "LD24") (pin "4") (pinfunction "A_4") (pintype "passive"))
      (node (ref "R83") (pin "2") (pinfunction "2_2") (pintype "passive"))
    )
    (net (code "52") (name "Net-(LD24C-A)") (class "Default")
      (node (ref "LD24") (pin "6") (pinfunction "A_6") (pintype "passive"))
      (node (ref "R89") (pin "2") (pinfunction "2_2") (pintype "passive"))
    )
    (net (code "53") (name "Net-(LD24D-A)") (class "Default")
      (node (ref "LD24") (pin "8") (pinfunction "A_8") (pintype "passive"))
      (node (ref "R95") (pin "2") (pinfunction "2_2") (pintype "passive"))
    )
    (net (code "54") (name "Net-(LD25A-A)") (class "Default")
      (node (ref "LD25") (pin "2") (pinfunction "A_2") (pintype "passive"))
      (node (ref "R96") (pin "2") (pinfunction "2_2") (pintype "passive"))
    )
    (net (code "55") (name "Net-(LD25B-A)") (class "Default")
      (node (ref "LD25") (pin "4") (pinfunction "A_4") (pintype "passive"))
      (node (ref "R98") (pin "2") (pinfunction "2_2") (pintype "passive"))
    )
    (net (code "56") (name "Net-(LD25C-A)") (class "Default")
      (node (ref "LD25") (pin "6") (pinfunction "A_6") (pintype "passive"))
      (node (ref "R99") (pin "2") (pinfunction "2_2") (pintype "passive"))
    )
    (net (code "57") (name "Net-(LD25D-A)") (class "Default")
      (node (ref "LD25") (pin "8") (pinfunction "A_8") (pintype "passive"))
      (node (ref "R100") (pin "2") (pinfunction "2_2") (pintype "passive"))
    )
    (net (code "58") (name "Net-(R101-Pad1)") (class "Default")
      (node (ref "R101") (pin "1") (pinfunction "1_1") (pintype "passive"))
      (node (ref "TP2") (pin "1") (pinfunction "1_1") (pintype "bidirectional"))
    )
    (net (code "59") (name "Net-(R102-Pad1)") (class "Default")
      (node (ref "R102") (pin "1") (pinfunction "1_1") (pintype "passive"))
      (node (ref "TP1") (pin "1") (pinfunction "1_1") (pintype "bidirectional"))
    )
    (net (code "60") (name "Net-(R102-Pad2)") (class "Default")
      (node (ref "R102") (pin "2") (pinfunction "2_2") (pintype "passive"))
      (node (ref "TP3") (pin "1") (pinfunction "1_1") (pintype "bidirectional"))
    )
    (net (code "61") (name "Net-(R103-Pad1)") (class "Default")
      (node (ref "R103") (pin "1") (pinfunction "1_1") (pintype "passive"))
      (node (ref "TP5") (pin "1") (pinfunction "1_1") (pintype "bidirectional"))
    )
    (net (code "62") (name "Net-(R104-Pad1)") (class "Default")
      (node (ref "R104") (pin "1") (pinfunction "1_1") (pintype "passive"))
      (node (ref "TP4") (pin "1") (pinfunction "1_1") (pintype "bidirectional"))
    )
    (net (code "63") (name "Net-(R104-Pad2)") (class "Default")
      (node (ref "R104") (pin "2") (pinfunction "2_2") (pintype "passive"))
      (node (ref "TP6") (pin "1") (pinfunction "1_1") (pintype "bidirectional"))
    )
    (net (code "64") (name "Net-(T1-D)") (class "Default")
      (node (ref "R31") (pin "1") (pinfunction "1_1") (pintype "passive"))
      (node (ref "R37") (pin "1") (pinfunction "1_1") (pintype "passive"))
      (node (ref "R92") (pin "1") (pinfunction "1_1") (pintype "passive"))
      (node (ref "T1") (pin "3") (pinfunction "D_3") (pintype "passive"))
    )
    (net (code "65") (name "Net-(T2-D)") (class "Default")
      (node (ref "R116") (pin "1") (pinfunction "1_1") (pintype "passive"))
      (node (ref "R117") (pin "1") (pinfunction "1_1") (pintype "passive"))
      (node (ref "R28") (pin "1") (pinfunction "1_1") (pintype "passive"))
      (node (ref "T2") (pin "3") (pinfunction "D_3") (pintype "passive"))
    )
    (net (code "66") (name "Net-(T5-D)") (class "Default")
      (node (ref "R106") (pin "1") (pinfunction "1_1") (pintype "passive"))
      (node (ref "R108") (pin "1") (pinfunction "1_1") (pintype "passive"))
      (node (ref "R111") (pin "1") (pinfunction "1_1") (pintype "passive"))
      (node (ref "T5") (pin "3") (pinfunction "D_3") (pintype "passive"))
    )
    (net (code "67") (name "Net-(T6-D)") (class "Default")
      (node (ref "R113") (pin "1") (pinfunction "1_1") (pintype "passive"))
      (node (ref "R114") (pin "1") (pinfunction "1_1") (pintype "passive"))
      (node (ref "R115") (pin "1") (pinfunction "1_1") (pintype "passive"))
      (node (ref "T6") (pin "3") (pinfunction "D_3") (pintype "passive"))
    )
    (net (code "68") (name "P3V3") (class "Default")
      (node (ref "C13") (pin "1") (pinfunction "1_1") (pintype "passive"))
      (node (ref "C186") (pin "1") (pinfunction "1_1") (pintype "passive"))
      (node (ref "C202") (pin "2") (pinfunction "2_2") (pintype "passive"))
      (node (ref "C297") (pin "2") (pinfunction "2_2") (pintype "passive"))
      (node (ref "C306") (pin "1") (pinfunction "1_1") (pintype "passive"))
      (node (ref "C307") (pin "1") (pinfunction "1_1") (pintype "passive"))
      (node (ref "C314") (pin "1") (pinfunction "1_1") (pintype "passive"))
      (node (ref "C315") (pin "2") (pinfunction "2_2") (pintype "passive"))
      (node (ref "C320") (pin "2") (pinfunction "2_2") (pintype "passive"))
      (node (ref "D2") (pin "2") (pinfunction "C_2") (pintype "passive"))
      (node (ref "D3") (pin "2") (pinfunction "C_2") (pintype "passive"))
      (node (ref "D4") (pin "2") (pinfunction "C_2") (pintype "passive"))
      (node (ref "D5") (pin "2") (pinfunction "C_2") (pintype "passive"))
      (node (ref "IC16") (pin "11") (pinfunction "LE_11") (pintype "input"))
      (node (ref "IC16") (pin "18") (pinfunction "VCC_18") (pintype "power_in"))
      (node (ref "IC16") (pin "25") (pinfunction "VCC_25") (pintype "power_in"))
      (node (ref "IC16") (pin "31") (pinfunction "VCC_31") (pintype "power_in"))
      (node (ref "IC16") (pin "35") (pinfunction "VCC_35") (pintype "power_in"))
      (node (ref "IC16") (pin "38") (pinfunction "VCC_38") (pintype "power_in"))
      (node (ref "IC16") (pin "42") (pinfunction "VCC_42") (pintype "power_in"))
      (node (ref "IC16") (pin "44") (pinfunction "BIASVCC_44") (pintype "input"))
      (node (ref "IC16") (pin "47") (pinfunction "VCC_47") (pintype "input"))
      (node (ref "IC16") (pin "7") (pinfunction "VCC_7") (pintype "power_in"))
      (node (ref "IC20") (pin "1") (pinfunction "VCC_1") (pintype "power_in"))
      (node (ref "L11") (pin "1") (pinfunction "1_1") (pintype "passive"))
      (node (ref "L5") (pin "1") (pinfunction "1_1") (pintype "passive"))
      (node (ref "R100") (pin "1") (pinfunction "1_1") (pintype "passive"))
      (node (ref "R400") (pin "2") (pinfunction "2_2") (pintype "passive"))
      (node (ref "R401") (pin "2") (pinfunction "2_2") (pintype "passive"))
      (node (ref "R402") (pin "2") (pinfunction "2_2") (pintype "passive"))
      (node (ref "R403") (pin "2") (pinfunction "2_2") (pintype "passive"))
      (node (ref "R404") (pin "2") (pinfunction "2_2") (pintype "passive"))
      (node (ref "R82") (pin "1") (pinfunction "1_1") (pintype "passive"))
      (node (ref "R83") (pin "1") (pinfunction "1_1") (pintype "passive"))
      (node (ref "R86") (pin "1") (pinfunction "1_1") (pintype "passive"))
      (node (ref "R89") (pin "1") (pinfunction "1_1") (pintype "passive"))
      (node (ref "R95") (pin "1") (pinfunction "1_1") (pintype "passive"))
      (node (ref "R96") (pin "1") (pinfunction "1_1") (pintype "passive"))
      (node (ref "R98") (pin "1") (pinfunction "1_1") (pintype "passive"))
      (node (ref "R99") (pin "1") (pinfunction "1_1") (pintype "passive"))
    )
    (net (code "69") (name "unconnected-(IC16-3A2-Pad12)") (class "Default")
      (node (ref "IC16") (pin "12") (pinfunction "3A2_12") (pintype "bidirectional"))
    )
    (net (code "70") (name "unconnected-(IC16-3A3-Pad13)") (class "Default")
      (node (ref "IC16") (pin "13") (pinfunction "3A3_13") (pintype "bidirectional"))
    )
    (net (code "71") (name "unconnected-(IC16-3A4-Pad16)") (class "Default")
      (node (ref "IC16") (pin "16") (pinfunction "3A4_16") (pintype "bidirectional"))
    )
    (net (code "72") (name "unconnected-(IC16-3A6-Pad20)") (class "Default")
      (node (ref "IC16") (pin "20") (pinfunction "3A6_20") (pintype "bidirectional"))
    )
    (net (code "73") (name "unconnected-(IC16-3A7-Pad22)") (class "Default")
      (node (ref "IC16") (pin "22") (pinfunction "3A7_22") (pintype "bidirectional"))
    )
    (net (code "74") (name "unconnected-(IC16-3A8-Pad23)") (class "Default")
      (node (ref "IC16") (pin "23") (pinfunction "3A8_23") (pintype "bidirectional"))
    )
    (net (code "75") (name "unconnected-(IC16-3B2-Pad37)") (class "Default")
      (node (ref "IC16") (pin "37") (pinfunction "3B2_37") (pintype "bidirectional"))
    )
    (net (code "76") (name "unconnected-(IC16-3B3-Pad36)") (class "Default")
      (node (ref "IC16") (pin "36") (pinfunction "3B3_36") (pintype "bidirectional"))
    )
    (net (code "77") (name "unconnected-(IC16-3B4-Pad33)") (class "Default")
      (node (ref "IC16") (pin "33") (pinfunction "3B4_33") (pintype "bidirectional"))
    )
    (net (code "78") (name "unconnected-(IC16-3B6-Pad29)") (class "Default")
      (node (ref "IC16") (pin "29") (pinfunction "3B6_29") (pintype "bidirectional"))
    )
    (net (code "79") (name "unconnected-(IC16-3B7-Pad27)") (class "Default")
      (node (ref "IC16") (pin "27") (pinfunction "3B7_27") (pintype "bidirectional"))
    )
    (net (code "80") (name "unconnected-(IC16-3B8-Pad26)") (class "Default")
      (node (ref "IC16") (pin "26") (pinfunction "3B8_26") (pintype "bidirectional"))
    )
  )
)
